# Homework.net
KiCad netlist of a schematic drawn in Altium Designer
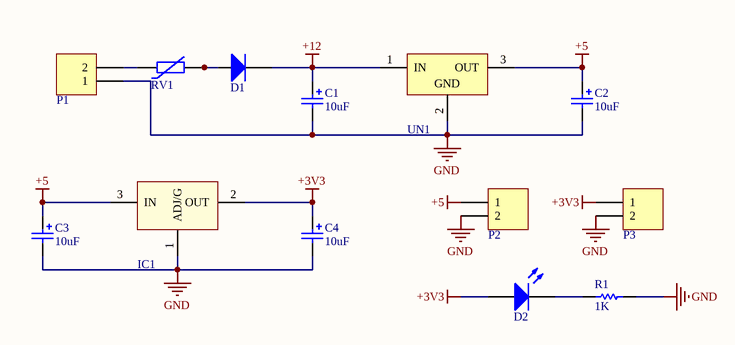
[diagram p0: Homework.SchDoc]

(export (version "E")
  (design (tool "Eeschema 10.0.6"))
  (components
    (comp (ref "C1")
      (value "10uF")
      (footprint "CP1/2")
      (description "Polarized Capacitor (Radial)")
      (fields (field (name "Comment") "Cap Pol"))
      (libsource (lib "PIF_Library") (part "Cap Pol"))
    )
    (comp (ref "C2")
      (value "10uF")
      (footprint "CP1/2")
      (description "Polarized Capacitor (Radial)")
      (fields (field (name "Comment") "Cap Pol"))
      (libsource (lib "PIF_Library") (part "Cap Pol"))
    )
    (comp (ref "C3")
      (value "10uF")
      (footprint "CP1/2")
      (description "Polarized Capacitor (Radial)")
      (fields (field (name "Comment") "Cap Pol"))
      (libsource (lib "PIF_Library") (part "Cap Pol"))
    )
    (comp (ref "C4")
      (value "10uF")
      (footprint "CP1/2")
      (description "Polarized Capacitor (Radial)")
      (fields (field (name "Comment") "Cap Pol"))
      (libsource (lib "PIF_Library") (part "Cap Pol"))
    )
    (comp (ref "D1")
      (value "Diode")
      (footprint "D1A")
      (description "Default Diode")
      (libsource (lib "PIF_Library") (part "Diode"))
    )
    (comp (ref "D2") (value "LED") (footprint "LED-3mm") (libsource (lib "PIF_Library") (part "LED")))
    (comp (ref "IC1")
      (value "LM1117")
      (footprint "QTO-220")
      (description "Available in 1.8V, 2.5V, 2.85V, 3.3V, 5V, and  Adjustable Versions")
      (libsource (lib "PIF_Library") (part "LM1117"))
    )
    (comp (ref "P1")
      (value "Domino 2")
      (footprint "DOMINO 2- 5mm")
      (description "Domino, 2-Pin")
      (fields (field (name "PUBLISHER") "Altium Limited"))
      (libsource (lib "") (part "Domino 2_1"))
    )
    (comp (ref "P2")
      (value "Domino 2")
      (footprint "DOMINO 2- 5mm")
      (description "Domino, 2-Pin")
      (fields (field (name "PUBLISHER") "Altium Limited"))
      (libsource (lib "PIF_Library") (part "Domino 2"))
    )
    (comp (ref "P3")
      (value "Domino 2")
      (footprint "DOMINO 2- 5mm")
      (description "Domino, 2-Pin")
      (fields (field (name "PUBLISHER") "Altium Limited"))
      (libsource (lib "PIF_Library") (part "Domino 2"))
    )
    (comp (ref "R1")
      (value "1K")
      (footprint "RES 1/2W")
      (description "Resistor")
      (fields (field (name "Comment") "RESISTOR"))
      (libsource (lib "PIF_Library") (part "RESISTOR"))
    )
    (comp (ref "RV1")
      (value "14VAC, 18VDC")
      (footprint "D9W4.5H12P0.8")
      (description "WE-VD Disk Varistor, THT, 14VAC, 18VDC, 2930pF")
      (fields
        (field (name "MANUFACTURER PART NUMBER") "820571406")
        (field (name "MANUFACTURER") "Wurth Elektronik")
      )
      (libsource (lib "Altium_WE-VD-rev23a") (part "820571406"))
    )
    (comp (ref "UN1")
      (value "LM7805")
      (footprint "QTO-220")
      (description "Positive Voltage Regulator")
      (libsource (lib "PIF_Library") (part "LM7805"))
    )
  )
  (nets
    (net (code "1") (name "+3V3") (class "Default")
      (node (ref "C4") (pin "1") (pinfunction "1_1") (pintype "passive"))
      (node (ref "D2") (pin "1") (pinfunction "A_1") (pintype "passive"))
      (node (ref "IC1") (pin "2") (pinfunction "OUT_2") (pintype "passive"))
      (node (ref "P3") (pin "1") (pinfunction "1_1") (pintype "passive"))
    )
    (net (code "2") (name "+5") (class "Default")
      (node (ref "C2") (pin "1") (pinfunction "1_1") (pintype "passive"))
      (node (ref "C3") (pin "1") (pinfunction "1_1") (pintype "passive"))
      (node (ref "IC1") (pin "3") (pinfunction "IN_3") (pintype "passive"))
      (node (ref "P2") (pin "1") (pinfunction "1_1") (pintype "passive"))
      (node (ref "UN1") (pin "3") (pinfunction "OUT_3") (pintype "power_in"))
    )
    (net (code "3") (name "+12") (class "Default")
      (node (ref "C1") (pin "1") (pinfunction "1_1") (pintype "passive"))
      (node (ref "D1") (pin "2") (pinfunction "K_2") (pintype "passive"))
      (node (ref "UN1") (pin "1") (pinfunction "IN_1") (pintype "power_in"))
    )
    (net (code "4") (name "GND") (class "Default")
      (node (ref "C1") (pin "2") (pinfunction "2_2") (pintype "passive"))
      (node (ref "C2") (pin "2") (pinfunction "2_2") (pintype "passive"))
      (node (ref "C3") (pin "2") (pinfunction "2_2") (pintype "passive"))
      (node (ref "C4") (pin "2") (pinfunction "2_2") (pintype "passive"))
      (node (ref "IC1") (pin "1") (pinfunction "ADJ/G_1") (pintype "passive"))
      (node (ref "P1") (pin "1") (pinfunction "1_1") (pintype "passive"))
      (node (ref "P2") (pin "2") (pinfunction "2_2") (pintype "passive"))
      (node (ref "P3") (pin "2") (pinfunction "2_2") (pintype "passive"))
      (node (ref "R1") (pin "2") (pinfunction "2_2") (pintype "passive"))
      (node (ref "UN1") (pin "2") (pinfunction "GND_2") (pintype "power_in"))
    )
    (net (code "5") (name "Net-(D1-A)") (class "Default")
      (node (ref "D1") (pin "1") (pinfunction "A_1") (pintype "passive"))
      (node (ref "RV1") (pin "2") (pinfunction "2_2") (pintype "passive"))
    )
    (net (code "6") (name "Net-(D2-K)") (class "Default")
      (node (ref "D2") (pin "2") (pinfunction "K_2") (pintype "passive"))
      (node (ref "R1") (pin "1") (pinfunction "1_1") (pintype "passive"))
    )
    (net (code "7") (name "Net-(P1-Pad2)") (class "Default")
      (node (ref "P1") (pin "2") (pinfunction "2_2") (pintype "passive"))
      (node (ref "RV1") (pin "1") (pinfunction "1_1") (pintype "passive"))
    )
  )
)
